# Interface.net
KiCad netlist of a schematic drawn in Altium Designer
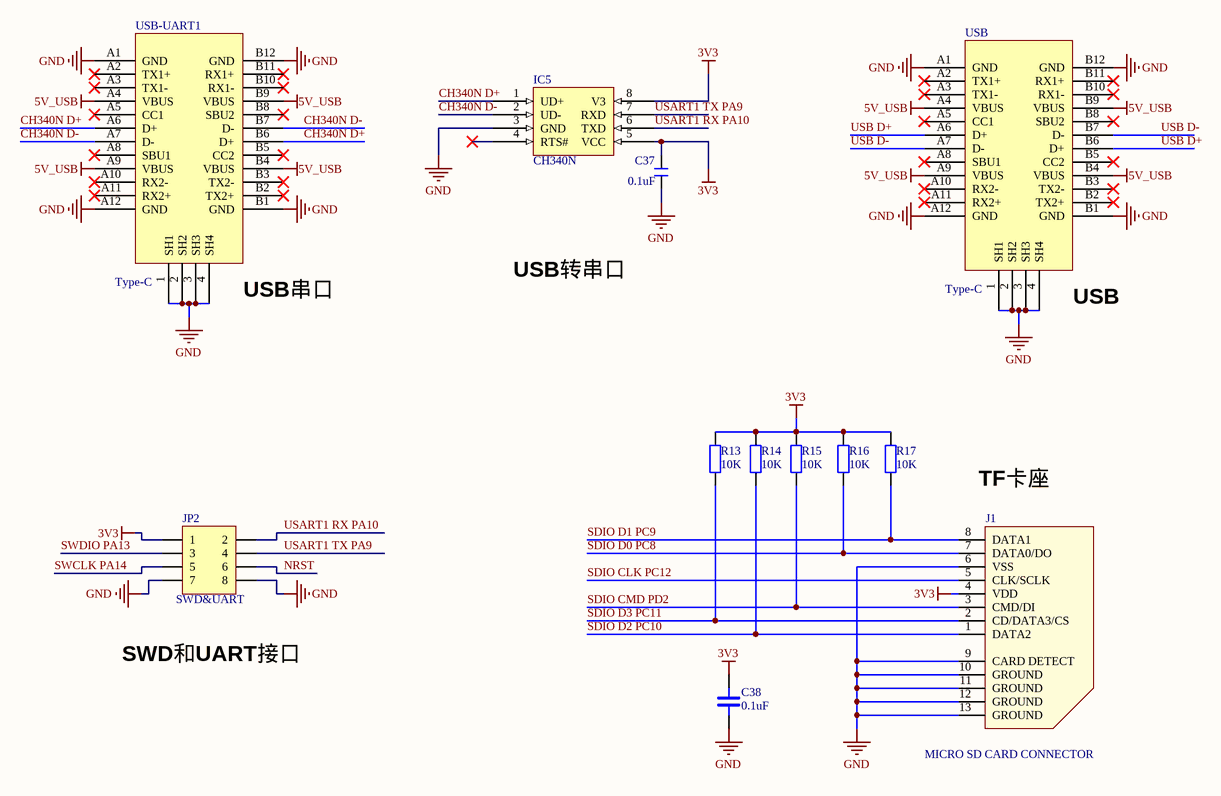
[diagram p0: Interface.SchDoc]

(export (version "E")
  (design (tool "Eeschema 10.0.6"))
  (components
    (comp (ref "C37")
      (value "0.1uF")
      (footprint "C 0603_M")
      (description "无极性贴片电容")
      (fields (field (name "版权归属") "源创客"))
      (libsource (lib "altium-import") (part "root_1_C_"))
    )
    (comp (ref "C38")
      (value "0.1uF")
      (footprint "C 0603_M")
      (description "Capacitor")
      (libsource (lib "General") (part "CAP"))
    )
    (comp (ref "IC5")
      (value "CH340N")
      (footprint "SOP8_M")
      (description "USB 转串口芯片 CH330/CH340N")
      (libsource (lib "altium-import") (part "root_0_CH340N_"))
    )
    (comp (ref "J1")
      (value "MICRO SD CARD CONNECTOR")
      (footprint "Micro SD")
      (description "Micro SD Card Connector")
      (libsource (lib "General") (part "MICRO SD CARD CONNECTOR"))
    )
    (comp (ref "JP2")
      (value "SWD&UART")
      (footprint "HDR2.54-LI-2x4P")
      (description "4*2P接插件")
      (fields (field (name "版权归属") "源创客"))
      (libsource (lib "4.5   - 接插件-脚距2.54") (part "Header 4X2"))
    )
    (comp (ref "R13")
      (value "10K")
      (footprint "R 0603_M")
      (description "Resistor")
      (libsource (lib "General") (part "RES"))
    )
    (comp (ref "R14")
      (value "10K")
      (footprint "R 0603_M")
      (description "Resistor")
      (libsource (lib "General") (part "RES"))
    )
    (comp (ref "R15")
      (value "10K")
      (footprint "R 0603_M")
      (description "Resistor")
      (libsource (lib "General") (part "RES"))
    )
    (comp (ref "R16")
      (value "10K")
      (footprint "R 0603_M")
      (description "Resistor")
      (libsource (lib "General") (part "RES"))
    )
    (comp (ref "R17")
      (value "10K")
      (footprint "R 0603_M")
      (description "Resistor")
      (libsource (lib "General") (part "RES"))
    )
    (comp (ref "USB")
      (value "Type-C")
      (footprint "Type-C")
      (libsource (lib "altium-import") (part "root_0_Type-C_"))
    )
    (comp (ref "USB-UART1")
      (value "Type-C")
      (footprint "Type-C")
      (libsource (lib "altium-import") (part "root_0_Type-C_"))
    )
  )
  (nets
    (net (code "1") (name "/CH340N D+") (class "Default")
      (node (ref "IC5") (pin "1") (pinfunction "UD+_1") (pintype "input"))
      (node (ref "USB-UART1") (pin "A6") (pinfunction "D+_A6") (pintype "passive"))
      (node (ref "USB-UART1") (pin "B6") (pinfunction "D+_B6") (pintype "passive"))
    )
    (net (code "2") (name "/CH340N D-") (class "Default")
      (node (ref "IC5") (pin "2") (pinfunction "UD-_2") (pintype "input"))
      (node (ref "USB-UART1") (pin "A7") (pinfunction "D-_A7") (pintype "passive"))
      (node (ref "USB-UART1") (pin "B7") (pinfunction "D-_B7") (pintype "passive"))
    )
    (net (code "3") (name "/NRST") (class "Default")
      (node (ref "JP2") (pin "6") (pinfunction "6_6") (pintype "passive"))
    )
    (net (code "4") (name "/SDIO CLK PC12") (class "Default")
      (node (ref "J1") (pin "5") (pinfunction "CLK/SCLK_5") (pintype "passive"))
    )
    (net (code "5") (name "/SDIO CMD PD2") (class "Default")
      (node (ref "J1") (pin "3") (pinfunction "CMD/DI_3") (pintype "passive"))
      (node (ref "R15") (pin "2") (pinfunction "2_2") (pintype "passive"))
    )
    (net (code "6") (name "/SDIO D0 PC8") (class "Default")
      (node (ref "J1") (pin "7") (pinfunction "DATA0/DO_7") (pintype "passive"))
      (node (ref "R16") (pin "2") (pinfunction "2_2") (pintype "passive"))
    )
    (net (code "7") (name "/SDIO D1 PC9") (class "Default")
      (node (ref "J1") (pin "8") (pinfunction "DATA1_8") (pintype "passive"))
      (node (ref "R17") (pin "2") (pinfunction "2_2") (pintype "passive"))
    )
    (net (code "8") (name "/SDIO D2 PC10") (class "Default")
      (node (ref "J1") (pin "1") (pinfunction "DATA2_1") (pintype "passive"))
      (node (ref "R14") (pin "2") (pinfunction "2_2") (pintype "passive"))
    )
    (net (code "9") (name "/SDIO D3 PC11") (class "Default")
      (node (ref "J1") (pin "2") (pinfunction "CD/DATA3/CS_2") (pintype "passive"))
      (node (ref "R13") (pin "2") (pinfunction "2_2") (pintype "passive"))
    )
    (net (code "10") (name "/SWCLK PA14") (class "Default")
      (node (ref "JP2") (pin "5") (pinfunction "5_5") (pintype "passive"))
    )
    (net (code "11") (name "/SWDIO PA13") (class "Default")
      (node (ref "JP2") (pin "3") (pinfunction "3_3") (pintype "passive"))
    )
    (net (code "12") (name "/USART1 RX PA10") (class "Default")
      (node (ref "IC5") (pin "6") (pinfunction "TXD_6") (pintype "input"))
      (node (ref "JP2") (pin "2") (pinfunction "2_2") (pintype "passive"))
    )
    (net (code "13") (name "/USART1 TX PA9") (class "Default")
      (node (ref "IC5") (pin "7") (pinfunction "RXD_7") (pintype "input"))
      (node (ref "JP2") (pin "4") (pinfunction "4_4") (pintype "passive"))
    )
    (net (code "14") (name "/USB D+") (class "Default")
      (node (ref "USB") (pin "A6") (pinfunction "D+_A6") (pintype "passive"))
      (node (ref "USB") (pin "B6") (pinfunction "D+_B6") (pintype "passive"))
    )
    (net (code "15") (name "/USB D-") (class "Default")
      (node (ref "USB") (pin "A7") (pinfunction "D-_A7") (pintype "passive"))
      (node (ref "USB") (pin "B7") (pinfunction "D-_B7") (pintype "passive"))
    )
    (net (code "16") (name "3V3") (class "Default")
      (node (ref "C37") (pin "2") (pinfunction "2_2") (pintype "passive"))
      (node (ref "C38") (pin "1") (pinfunction "1_1") (pintype "passive"))
      (node (ref "IC5") (pin "5") (pinfunction "VCC_5") (pintype "input"))
      (node (ref "IC5") (pin "8") (pinfunction "V3_8") (pintype "input"))
      (node (ref "J1") (pin "4") (pinfunction "VDD_4") (pintype "power_in"))
      (node (ref "JP2") (pin "1") (pinfunction "1_1") (pintype "passive"))
      (node (ref "R13") (pin "1") (pinfunction "1_1") (pintype "passive"))
      (node (ref "R14") (pin "1") (pinfunction "1_1") (pintype "passive"))
      (node (ref "R15") (pin "1") (pinfunction "1_1") (pintype "passive"))
      (node (ref "R16") (pin "1") (pinfunction "1_1") (pintype "passive"))
      (node (ref "R17") (pin "1") (pinfunction "1_1") (pintype "passive"))
    )
    (net (code "17") (name "5V_USB") (class "Default")
      (node (ref "USB") (pin "A4") (pinfunction "VBUS_A4") (pintype "passive"))
      (node (ref "USB") (pin "A9") (pinfunction "VBUS_A9") (pintype "passive"))
      (node (ref "USB") (pin "B4") (pinfunction "VBUS_B4") (pintype "passive"))
      (node (ref "USB") (pin "B9") (pinfunction "VBUS_B9") (pintype "passive"))
      (node (ref "USB-UART1") (pin "A4") (pinfunction "VBUS_A4") (pintype "passive"))
      (node (ref "USB-UART1") (pin "A9") (pinfunction "VBUS_A9") (pintype "passive"))
      (node (ref "USB-UART1") (pin "B4") (pinfunction "VBUS_B4") (pintype "passive"))
      (node (ref "USB-UART1") (pin "B9") (pinfunction "VBUS_B9") (pintype "passive"))
    )
    (net (code "18") (name "GND") (class "Default")
      (node (ref "C37") (pin "1") (pinfunction "1_1") (pintype "passive"))
      (node (ref "C38") (pin "2") (pinfunction "2_2") (pintype "passive"))
      (node (ref "IC5") (pin "3") (pinfunction "GND_3") (pintype "input"))
      (node (ref "J1") (pin "10") (pinfunction "GROUND_10") (pintype "passive"))
      (node (ref "J1") (pin "11") (pinfunction "GROUND_11") (pintype "passive"))
      (node (ref "J1") (pin "12") (pinfunction "GROUND_12") (pintype "passive"))
      (node (ref "J1") (pin "13") (pinfunction "GROUND_13") (pintype "passive"))
      (node (ref "J1") (pin "6") (pinfunction "VSS_6") (pintype "power_in"))
      (node (ref "J1") (pin "9") (pinfunction "CARD_DETECT_9") (pintype "passive"))
      (node (ref "JP2") (pin "7") (pinfunction "7_7") (pintype "passive"))
      (node (ref "JP2") (pin "8") (pinfunction "8_8") (pintype "passive"))
      (node (ref "USB") (pin "1") (pinfunction "SH1_1") (pintype "passive"))
      (node (ref "USB") (pin "2") (pinfunction "SH2_2") (pintype "passive"))
      (node (ref "USB") (pin "3") (pinfunction "SH3_3") (pintype "passive"))
      (node (ref "USB") (pin "4") (pinfunction "SH4_4") (pintype "passive"))
      (node (ref "USB") (pin "A1") (pinfunction "GND_A1") (pintype "passive"))
      (node (ref "USB") (pin "A12") (pinfunction "GND_A12") (pintype "passive"))
      (node (ref "USB") (pin "B1") (pinfunction "GND_B1") (pintype "passive"))
      (node (ref "USB") (pin "B12") (pinfunction "GND_B12") (pintype "passive"))
      (node (ref "USB-UART1") (pin "1") (pinfunction "SH1_1") (pintype "passive"))
      (node (ref "USB-UART1") (pin "2") (pinfunction "SH2_2") (pintype "passive"))
      (node (ref "USB-UART1") (pin "3") (pinfunction "SH3_3") (pintype "passive"))
      (node (ref "USB-UART1") (pin "4") (pinfunction "SH4_4") (pintype "passive"))
      (node (ref "USB-UART1") (pin "A1") (pinfunction "GND_A1") (pintype "passive"))
      (node (ref "USB-UART1") (pin "A12") (pinfunction "GND_A12") (pintype "passive"))
      (node (ref "USB-UART1") (pin "B1") (pinfunction "GND_B1") (pintype "passive"))
      (node (ref "USB-UART1") (pin "B12") (pinfunction "GND_B12") (pintype "passive"))
    )
    (net (code "19") (name "unconnected-(IC5-RTS#-Pad4)") (class "Default")
      (node (ref "IC5") (pin "4") (pinfunction "RTS#_4") (pintype "input+no_connect"))
    )
    (net (code "20") (name "unconnected-(USB-CC1-PadA5)") (class "Default")
      (node (ref "USB") (pin "A5") (pinfunction "CC1_A5") (pintype "passive+no_connect"))
    )
    (net (code "21") (name "unconnected-(USB-CC2-PadB5)") (class "Default")
      (node (ref "USB") (pin "B5") (pinfunction "CC2_B5") (pintype "passive+no_connect"))
    )
    (net (code "22") (name "unconnected-(USB-RX1+-PadB11)") (class "Default")
      (node (ref "USB") (pin "B11") (pinfunction "RX1+_B11") (pintype "passive+no_connect"))
    )
    (net (code "23") (name "unconnected-(USB-RX1--PadB10)") (class "Default")
      (node (ref "USB") (pin "B10") (pinfunction "RX1-_B10") (pintype "passive+no_connect"))
    )
    (net (code "24") (name "unconnected-(USB-RX2+-PadA11)") (class "Default")
      (node (ref "USB") (pin "A11") (pinfunction "RX2+_A11") (pintype "passive+no_connect"))
    )
    (net (code "25") (name "unconnected-(USB-RX2--PadA10)") (class "Default")
      (node (ref "USB") (pin "A10") (pinfunction "RX2-_A10") (pintype "passive+no_connect"))
    )
    (net (code "26") (name "unconnected-(USB-SBU1-PadA8)") (class "Default")
      (node (ref "USB") (pin "A8") (pinfunction "SBU1_A8") (pintype "passive+no_connect"))
    )
    (net (code "27") (name "unconnected-(USB-SBU2-PadB8)") (class "Default")
      (node (ref "USB") (pin "B8") (pinfunction "SBU2_B8") (pintype "passive+no_connect"))
    )
    (net (code "28") (name "unconnected-(USB-TX1+-PadA2)") (class "Default")
      (node (ref "USB") (pin "A2") (pinfunction "TX1+_A2") (pintype "passive+no_connect"))
    )
    (net (code "29") (name "unconnected-(USB-TX1--PadA3)") (class "Default")
      (node (ref "USB") (pin "A3") (pinfunction "TX1-_A3") (pintype "passive+no_connect"))
    )
    (net (code "30") (name "unconnected-(USB-TX2+-PadB2)") (class "Default")
      (node (ref "USB") (pin "B2") (pinfunction "TX2+_B2") (pintype "passive+no_connect"))
    )
    (net (code "31") (name "unconnected-(USB-TX2--PadB3)") (class "Default")
      (node (ref "USB") (pin "B3") (pinfunction "TX2-_B3") (pintype "passive+no_connect"))
    )
    (net (code "32") (name "unconnected-(USB-UART1-CC1-PadA5)") (class "Default")
      (node (ref "USB-UART1") (pin "A5") (pinfunction "CC1_A5") (pintype "passive+no_connect"))
    )
    (net (code "33") (name "unconnected-(USB-UART1-CC2-PadB5)") (class "Default")
      (node (ref "USB-UART1") (pin "B5") (pinfunction "CC2_B5") (pintype "passive+no_connect"))
    )
    (net (code "34") (name "unconnected-(USB-UART1-RX1+-PadB11)") (class "Default")
      (node (ref "USB-UART1") (pin "B11") (pinfunction "RX1+_B11") (pintype "passive+no_connect"))
    )
    (net (code "35") (name "unconnected-(USB-UART1-RX1--PadB10)") (class "Default")
      (node (ref "USB-UART1") (pin "B10") (pinfunction "RX1-_B10") (pintype "passive+no_connect"))
    )
    (net (code "36") (name "unconnected-(USB-UART1-RX2+-PadA11)") (class "Default")
      (node (ref "USB-UART1") (pin "A11") (pinfunction "RX2+_A11") (pintype "passive+no_connect"))
    )
    (net (code "37") (name "unconnected-(USB-UART1-RX2--PadA10)") (class "Default")
      (node (ref "USB-UART1") (pin "A10") (pinfunction "RX2-_A10") (pintype "passive+no_connect"))
    )
    (net (code "38") (name "unconnected-(USB-UART1-SBU1-PadA8)") (class "Default")
      (node (ref "USB-UART1") (pin "A8") (pinfunction "SBU1_A8") (pintype "passive+no_connect"))
    )
    (net (code "39") (name "unconnected-(USB-UART1-SBU2-PadB8)") (class "Default")
      (node (ref "USB-UART1") (pin "B8") (pinfunction "SBU2_B8") (pintype "passive+no_connect"))
    )
    (net (code "40") (name "unconnected-(USB-UART1-TX1+-PadA2)") (class "Default")
      (node (ref "USB-UART1") (pin "A2") (pinfunction "TX1+_A2") (pintype "passive+no_connect"))
    )
    (net (code "41") (name "unconnected-(USB-UART1-TX1--PadA3)") (class "Default")
      (node (ref "USB-UART1") (pin "A3") (pinfunction "TX1-_A3") (pintype "passive+no_connect"))
    )
    (net (code "42") (name "unconnected-(USB-UART1-TX2+-PadB2)") (class "Default")
      (node (ref "USB-UART1") (pin "B2") (pinfunction "TX2+_B2") (pintype "passive+no_connect"))
    )
    (net (code "43") (name "unconnected-(USB-UART1-TX2--PadB3)") (class "Default")
      (node (ref "USB-UART1") (pin "B3") (pinfunction "TX2-_B3") (pintype "passive+no_connect"))
    )
  )
)
